# Driver.net
KiCad netlist of a schematic drawn in Altium Designer
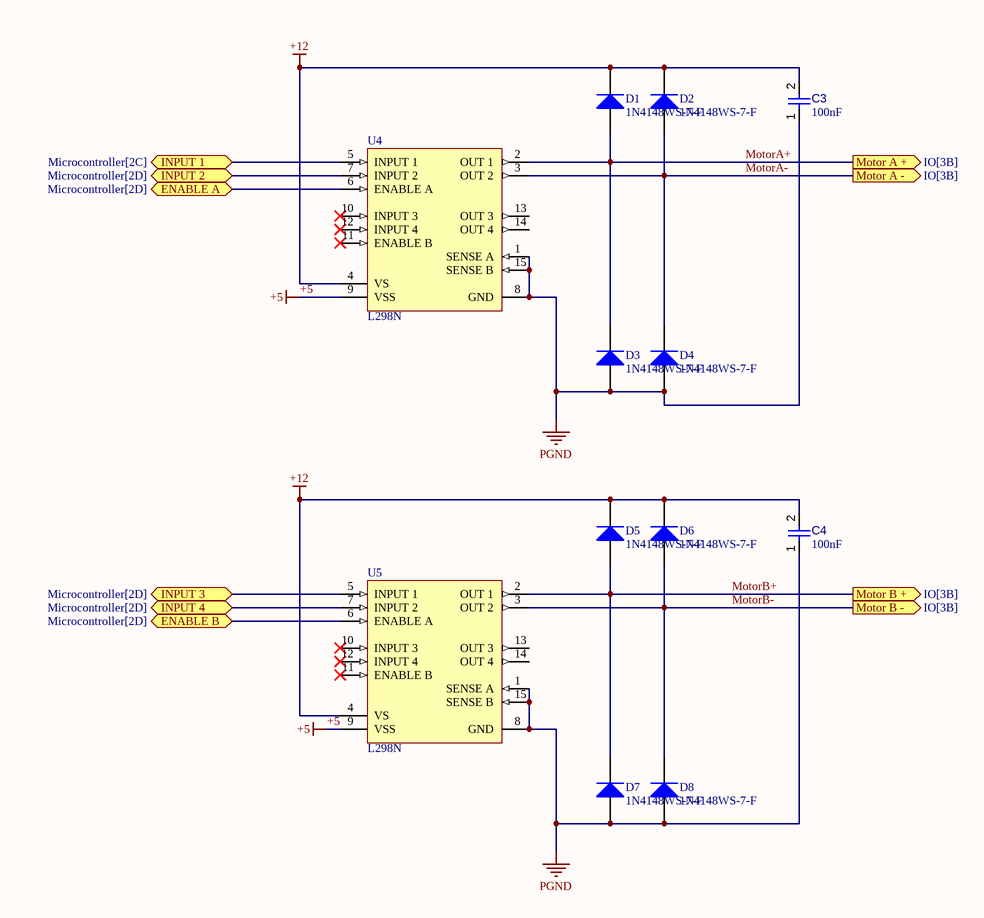
[diagram p0: Driver.SchDoc]

(export (version "E")
  (design (tool "Eeschema 10.0.6"))
  (components
    (comp (ref "C3")
      (value "100nF")
      (footprint "CAPC1608X90X40NL10T20")
      (description "Chip Capacitor, 100 nF, +/- 10%, 50 V, 0603 (1608 Metric)")
      (fields (field (name "TOLERANCE") "10%") (field (name "Comment") "Capacitor 100 nF +/-10% 50 V 0603"))
      (libsource (lib "Ryan Nedjabat") (part "CAP-NP-2"))
    )
    (comp (ref "C4")
      (value "100nF")
      (footprint "CAPC1608X90X40NL10T20")
      (description "Chip Capacitor, 100 nF, +/- 10%, 50 V, 0603 (1608 Metric)")
      (fields (field (name "TOLERANCE") "10%") (field (name "Comment") "Capacitor 100 nF +/-10% 50 V 0603"))
      (libsource (lib "Ryan Nedjabat") (part "CAP-NP-2"))
    )
    (comp (ref "D1")
      (value "1N4148WS-7-F")
      (footprint "DIOD-SOD323-2-A_V")
      (description "Fast Switching Diode, 75 V, 0.3 A, -65 to 150 degC, 2-Pin SOD323, RoHS, Tape and Reel")
      (libsource (lib "Altium Content Vault") (part "D-AK-2"))
    )
    (comp (ref "D2")
      (value "1N4148WS-7-F")
      (footprint "DIOD-SOD323-2-A_V")
      (description "Fast Switching Diode, 75 V, 0.3 A, -65 to 150 degC, 2-Pin SOD323, RoHS, Tape and Reel")
      (libsource (lib "Altium Content Vault") (part "D-AK-2"))
    )
    (comp (ref "D3")
      (value "1N4148WS-7-F")
      (footprint "DIOD-SOD323-2-A_V")
      (description "Fast Switching Diode, 75 V, 0.3 A, -65 to 150 degC, 2-Pin SOD323, RoHS, Tape and Reel")
      (libsource (lib "Altium Content Vault") (part "D-AK-2"))
    )
    (comp (ref "D4")
      (value "1N4148WS-7-F")
      (footprint "DIOD-SOD323-2-A_V")
      (description "Fast Switching Diode, 75 V, 0.3 A, -65 to 150 degC, 2-Pin SOD323, RoHS, Tape and Reel")
      (libsource (lib "Altium Content Vault") (part "D-AK-2"))
    )
    (comp (ref "D5")
      (value "1N4148WS-7-F")
      (footprint "DIOD-SOD323-2-A_V")
      (description "Fast Switching Diode, 75 V, 0.3 A, -65 to 150 degC, 2-Pin SOD323, RoHS, Tape and Reel")
      (libsource (lib "Altium Content Vault") (part "D-AK-2"))
    )
    (comp (ref "D6")
      (value "1N4148WS-7-F")
      (footprint "DIOD-SOD323-2-A_V")
      (description "Fast Switching Diode, 75 V, 0.3 A, -65 to 150 degC, 2-Pin SOD323, RoHS, Tape and Reel")
      (libsource (lib "Altium Content Vault") (part "D-AK-2"))
    )
    (comp (ref "D7")
      (value "1N4148WS-7-F")
      (footprint "DIOD-SOD323-2-A_V")
      (description "Fast Switching Diode, 75 V, 0.3 A, -65 to 150 degC, 2-Pin SOD323, RoHS, Tape and Reel")
      (libsource (lib "Altium Content Vault") (part "D-AK-2"))
    )
    (comp (ref "D8")
      (value "1N4148WS-7-F")
      (footprint "DIOD-SOD323-2-A_V")
      (description "Fast Switching Diode, 75 V, 0.3 A, -65 to 150 degC, 2-Pin SOD323, RoHS, Tape and Reel")
      (libsource (lib "Altium Content Vault") (part "D-AK-2"))
    )
    (comp (ref "U4")
      (value "L298N")
      (footprint "STM-FM-15")
      (description "Dual Full-Bridge Driver, 4.8 to 46 V, -40 to 150 degC, 15-Pin FM (MW 15L), RoHS, Tube")
      (fields (field (name "MANUFACTURER") "STMicroelectronics") (field (name "PARTNUMBER") "L298"))
      (libsource (lib "Altium Content Vault") (part "STM-L298-15"))
    )
    (comp (ref "U5")
      (value "L298N")
      (footprint "STM-FM-15")
      (description "Dual Full-Bridge Driver, 4.8 to 46 V, -40 to 150 degC, 15-Pin FM (MW 15L), RoHS, Tube")
      (fields (field (name "MANUFACTURER") "STMicroelectronics") (field (name "PARTNUMBER") "L298"))
      (libsource (lib "Altium Content Vault") (part "STM-L298-15"))
    )
  )
  (nets
    (net (code "1") (name "+5") (class "Default")
      (node (ref "U4") (pin "9") (pinfunction "VSS_9") (pintype "power_in"))
      (node (ref "U5") (pin "9") (pinfunction "VSS_9") (pintype "power_in"))
    )
    (net (code "2") (name "+12") (class "Default")
      (node (ref "C3") (pin "2") (pinfunction "2_2") (pintype "passive"))
      (node (ref "C4") (pin "2") (pinfunction "2_2") (pintype "passive"))
      (node (ref "D1") (pin "2") (pinfunction "K_2") (pintype "passive"))
      (node (ref "D2") (pin "2") (pinfunction "K_2") (pintype "passive"))
      (node (ref "D5") (pin "2") (pinfunction "K_2") (pintype "passive"))
      (node (ref "D6") (pin "2") (pinfunction "K_2") (pintype "passive"))
      (node (ref "U4") (pin "4") (pinfunction "VS_4") (pintype "power_in"))
      (node (ref "U5") (pin "4") (pinfunction "VS_4") (pintype "power_in"))
    )
    (net (code "3") (name "/ENABLE A") (class "Default")
      (node (ref "U4") (pin "6") (pinfunction "ENABLE_A_6") (pintype "input"))
    )
    (net (code "4") (name "/ENABLE B") (class "Default")
      (node (ref "U5") (pin "6") (pinfunction "ENABLE_A_6") (pintype "input"))
    )
    (net (code "5") (name "/INPUT 1") (class "Default")
      (node (ref "U4") (pin "5") (pinfunction "INPUT_1_5") (pintype "input"))
    )
    (net (code "6") (name "/INPUT 2") (class "Default")
      (node (ref "U4") (pin "7") (pinfunction "INPUT_2_7") (pintype "input"))
    )
    (net (code "7") (name "/INPUT 3") (class "Default")
      (node (ref "U5") (pin "5") (pinfunction "INPUT_1_5") (pintype "input"))
    )
    (net (code "8") (name "/INPUT 4") (class "Default")
      (node (ref "U5") (pin "7") (pinfunction "INPUT_2_7") (pintype "input"))
    )
    (net (code "9") (name "/MotorA+") (class "Default")
      (node (ref "D1") (pin "1") (pinfunction "A_1") (pintype "passive"))
      (node (ref "D3") (pin "2") (pinfunction "K_2") (pintype "passive"))
      (node (ref "U4") (pin "2") (pinfunction "OUT_1_2") (pintype "output"))
    )
    (net (code "10") (name "/MotorA-") (class "Default")
      (node (ref "D2") (pin "1") (pinfunction "A_1") (pintype "passive"))
      (node (ref "D4") (pin "2") (pinfunction "K_2") (pintype "passive"))
      (node (ref "U4") (pin "3") (pinfunction "OUT_2_3") (pintype "output"))
    )
    (net (code "11") (name "/MotorB+") (class "Default")
      (node (ref "D5") (pin "1") (pinfunction "A_1") (pintype "passive"))
      (node (ref "D7") (pin "2") (pinfunction "K_2") (pintype "passive"))
      (node (ref "U5") (pin "2") (pinfunction "OUT_1_2") (pintype "output"))
    )
    (net (code "12") (name "/MotorB-") (class "Default")
      (node (ref "D6") (pin "1") (pinfunction "A_1") (pintype "passive"))
      (node (ref "D8") (pin "2") (pinfunction "K_2") (pintype "passive"))
      (node (ref "U5") (pin "3") (pinfunction "OUT_2_3") (pintype "output"))
    )
    (net (code "13") (name "PGND") (class "Default")
      (node (ref "C3") (pin "1") (pinfunction "1_1") (pintype "passive"))
      (node (ref "C4") (pin "1") (pinfunction "1_1") (pintype "passive"))
      (node (ref "D3") (pin "1") (pinfunction "A_1") (pintype "passive"))
      (node (ref "D4") (pin "1") (pinfunction "A_1") (pintype "passive"))
      (node (ref "D7") (pin "1") (pinfunction "A_1") (pintype "passive"))
      (node (ref "D8") (pin "1") (pinfunction "A_1") (pintype "passive"))
      (node (ref "U4") (pin "1") (pinfunction "SENSE_A_1") (pintype "input"))
      (node (ref "U4") (pin "15") (pinfunction "SENSE_B_15") (pintype "input"))
      (node (ref "U4") (pin "8") (pinfunction "GND_8") (pintype "power_in"))
      (node (ref "U5") (pin "1") (pinfunction "SENSE_A_1") (pintype "input"))
      (node (ref "U5") (pin "15") (pinfunction "SENSE_B_15") (pintype "input"))
      (node (ref "U5") (pin "8") (pinfunction "GND_8") (pintype "power_in"))
    )
    (net (code "14") (name "unconnected-(U4-ENABLE_B-Pad11)") (class "Default")
      (node (ref "U4") (pin "11") (pinfunction "ENABLE_B_11") (pintype "input+no_connect"))
    )
    (net (code "15") (name "unconnected-(U4-INPUT_3-Pad10)") (class "Default")
      (node (ref "U4") (pin "10") (pinfunction "INPUT_3_10") (pintype "input+no_connect"))
    )
    (net (code "16") (name "unconnected-(U4-INPUT_4-Pad12)") (class "Default")
      (node (ref "U4") (pin "12") (pinfunction "INPUT_4_12") (pintype "input+no_connect"))
    )
    (net (code "17") (name "unconnected-(U4-OUT_3-Pad13)") (class "Default")
      (node (ref "U4") (pin "13") (pinfunction "OUT_3_13") (pintype "output"))
    )
    (net (code "18") (name "unconnected-(U4-OUT_4-Pad14)") (class "Default")
      (node (ref "U4") (pin "14") (pinfunction "OUT_4_14") (pintype "output"))
    )
    (net (code "19") (name "unconnected-(U5-ENABLE_B-Pad11)") (class "Default")
      (node (ref "U5") (pin "11") (pinfunction "ENABLE_B_11") (pintype "input+no_connect"))
    )
    (net (code "20") (name "unconnected-(U5-INPUT_3-Pad10)") (class "Default")
      (node (ref "U5") (pin "10") (pinfunction "INPUT_3_10") (pintype "input+no_connect"))
    )
    (net (code "21") (name "unconnected-(U5-INPUT_4-Pad12)") (class "Default")
      (node (ref "U5") (pin "12") (pinfunction "INPUT_4_12") (pintype "input+no_connect"))
    )
    (net (code "22") (name "unconnected-(U5-OUT_3-Pad13)") (class "Default")
      (node (ref "U5") (pin "13") (pinfunction "OUT_3_13") (pintype "output"))
    )
    (net (code "23") (name "unconnected-(U5-OUT_4-Pad14)") (class "Default")
      (node (ref "U5") (pin "14") (pinfunction "OUT_4_14") (pintype "output"))
    )
  )
)
